# ProPrj_LED__2025-12-08-14-26-45.net
KiCad netlist of a schematic drawn in EasyEDA Pro
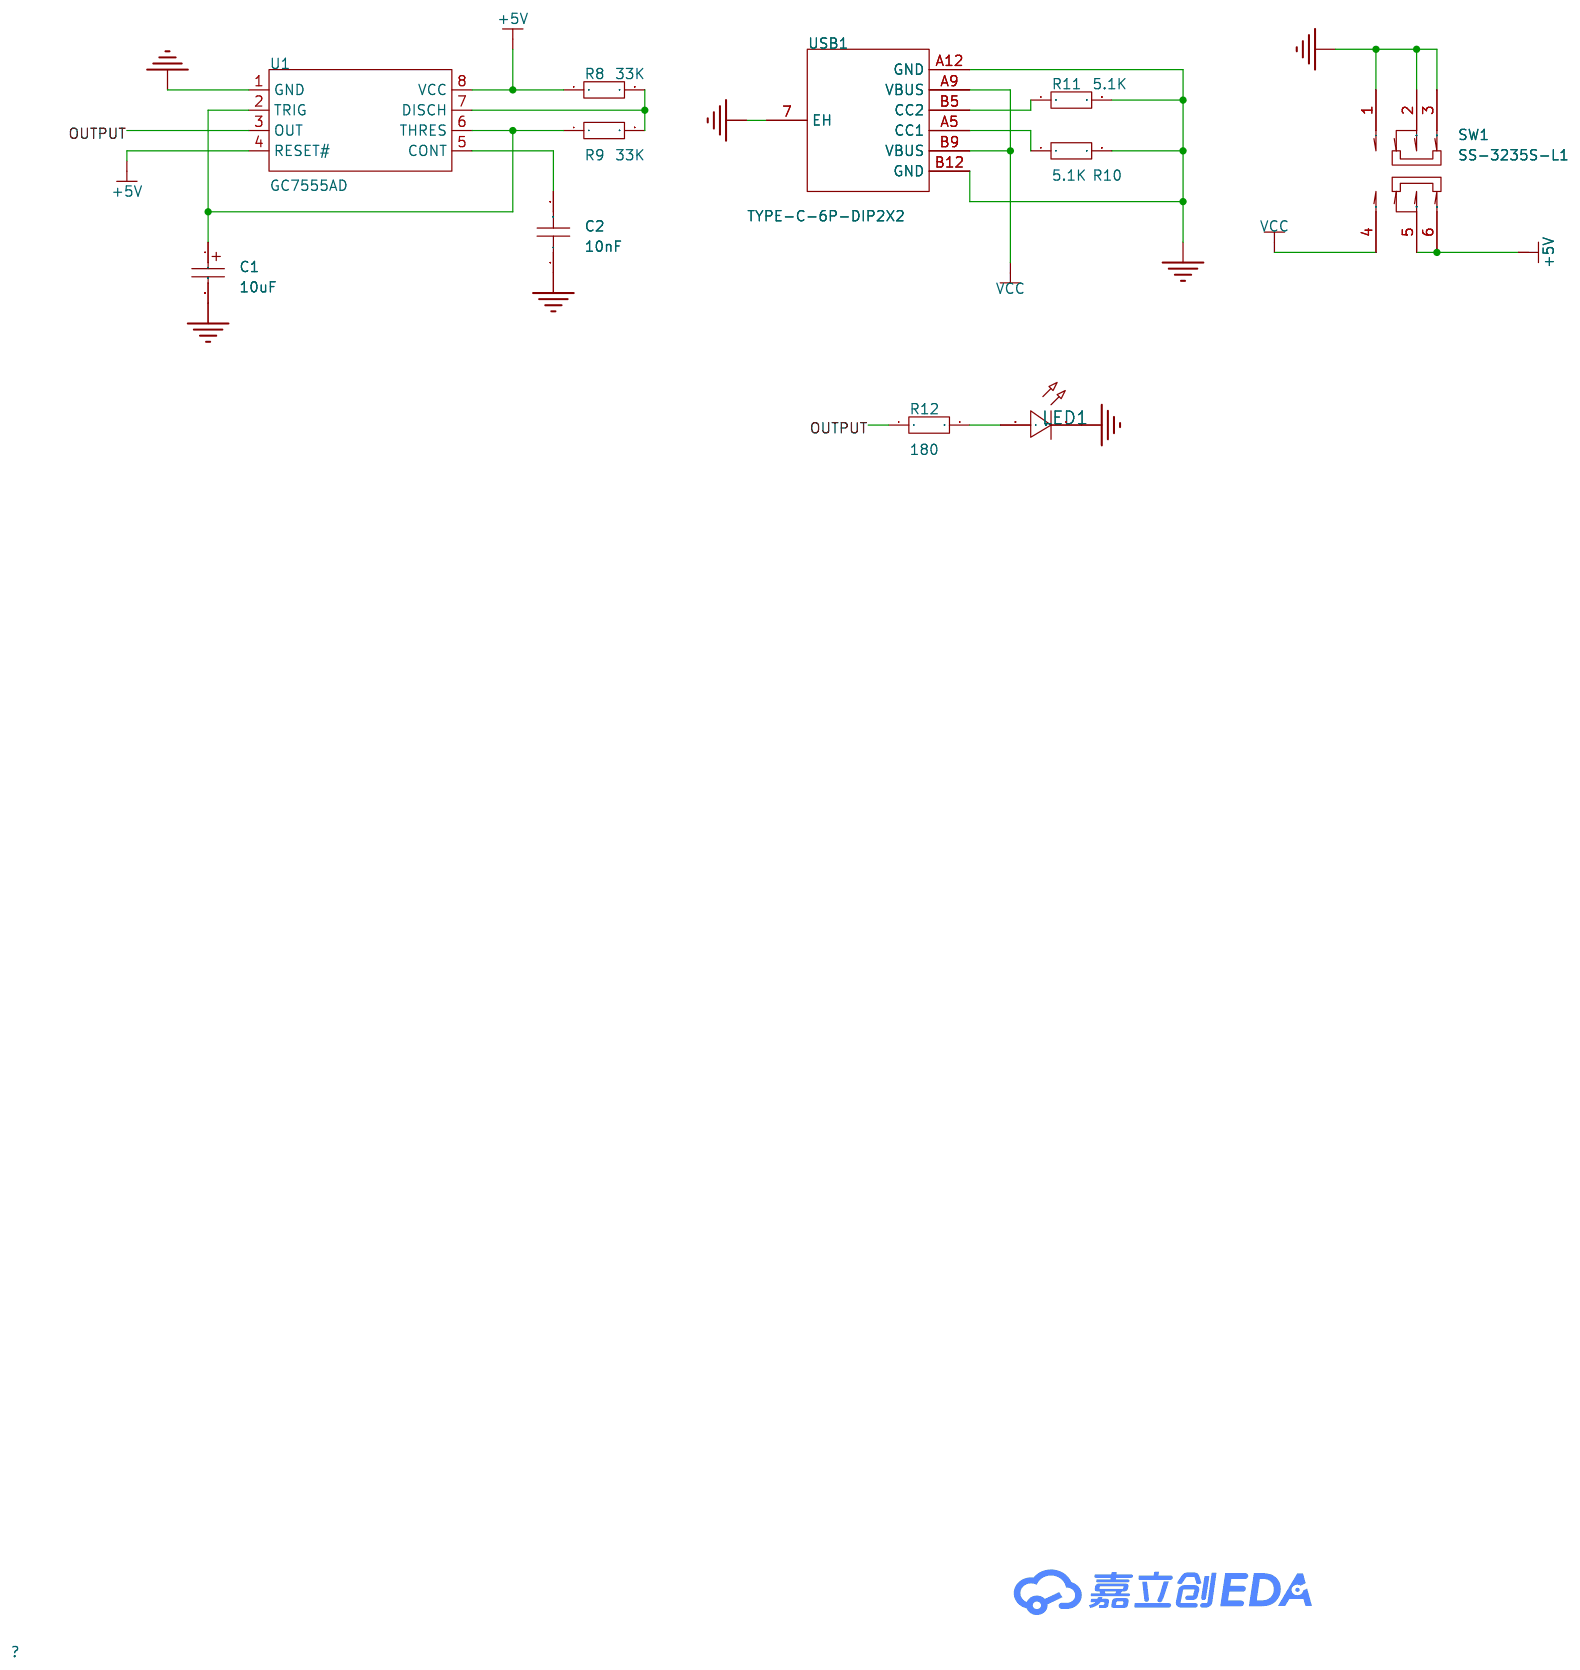
[diagram p0: schematic sheet]

(export (version "E")
  (design (tool "Eeschema 10.0.6"))
  (components
    (comp (ref "C1")
      (value "10uF")
      (footprint "easyedapro:C_Ele_SMD_3x5.4mm")
      (libsource (lib "easyedapro") (part "CAP"))
    )
    (comp (ref "C2")
      (value "10nF")
      (footprint "easyedapro:C0603")
      (libsource (lib "easyedapro") (part "Capacitance"))
    )
    (comp (ref "LED1")
      (value "~")
      (footprint "easyedapro:LED_0603")
      (libsource (lib "easyedapro") (part "LED_R"))
    )
    (comp (ref "R8") (value "33K") (footprint "easyedapro:R0805") (libsource (lib "easyedapro") (part "电阻")))
    (comp (ref "R9") (value "33K") (footprint "easyedapro:R0805") (libsource (lib "easyedapro") (part "电阻")))
    (comp (ref "R10")
      (value "5.1K")
      (footprint "easyedapro:R0805")
      (libsource (lib "easyedapro") (part "电阻"))
    )
    (comp (ref "R11")
      (value "5.1K")
      (footprint "easyedapro:R0805")
      (libsource (lib "easyedapro") (part "电阻"))
    )
    (comp (ref "R12") (value "180") (footprint "easyedapro:R0805") (libsource (lib "easyedapro") (part "电阻")))
    (comp (ref "SW1")
      (value "SS-3235S-L1")
      (footprint "easyedapro:SW-SMD_SS-3235S-LX")
      (description "电路结构:双刀双掷;安装方式:卧贴;开关颜色:黑色;额定电流:50mA;额定电压:12V;工作寿命:1万次;")
      (fields (field (name "Manufacturer") "XKB Connection(中国星坤)"))
      (libsource (lib "easyedapro") (part "SS-3235S-L1"))
    )
    (comp (ref "U1")
      (value "GC7555AD")
      (footprint "easyedapro:PDIP-8_L9.5-W6.4-P2.54-LS7.6-BL")
      (description "通用计时器：时基电路；计时；脉冲产生；满足用户（至少工业级）自主可控的需求。")
      (fields (field (name "Manufacturer") "Sungine(双竞集成)"))
      (libsource (lib "easyedapro") (part "GC7555AD"))
    )
    (comp (ref "USB1")
      (value "TYPE-C-6P-DIP2X2")
      (footprint "easyedapro:TYPE-C-SMD_TYPE-C-6P")
      (libsource (lib "easyedapro") (part "TYPE-C-6P-DIP2X2"))
    )
  )
  (nets
    (net (code "1") (name "+5V") (class "Default")
      (node (ref "R8") (pin "1") (pinfunction "1_1") (pintype "input"))
      (node (ref "SW1") (pin "5") (pinfunction "5_5") (pintype "unspecified"))
      (node (ref "SW1") (pin "6") (pinfunction "6_6") (pintype "unspecified"))
      (node (ref "U1") (pin "4") (pinfunction "RESET#_4") (pintype "unspecified"))
      (node (ref "U1") (pin "8") (pinfunction "VCC_8") (pintype "unspecified"))
    )
    (net (code "2") (name "/OUTPUT") (class "Default")
      (node (ref "R12") (pin "1") (pinfunction "1_1") (pintype "input"))
      (node (ref "U1") (pin "3") (pinfunction "OUT_3") (pintype "unspecified"))
    )
    (net (code "3") (name "GND") (class "Default")
      (node (ref "C1") (pin "2") (pinfunction "2_2") (pintype "input"))
      (node (ref "C2") (pin "1") (pinfunction "1_1") (pintype "input"))
      (node (ref "LED1") (pin "1") (pinfunction "C_1") (pintype "input"))
      (node (ref "R10") (pin "2") (pinfunction "2_2") (pintype "input"))
      (node (ref "R11") (pin "2") (pinfunction "2_2") (pintype "input"))
      (node (ref "SW1") (pin "1") (pinfunction "1_1") (pintype "unspecified"))
      (node (ref "SW1") (pin "2") (pinfunction "2_2") (pintype "unspecified"))
      (node (ref "SW1") (pin "3") (pinfunction "3_3") (pintype "unspecified"))
      (node (ref "U1") (pin "1") (pinfunction "GND_1") (pintype "unspecified"))
      (node (ref "USB1") (pin "7") (pinfunction "EH_7") (pintype "unspecified"))
      (node (ref "USB1") (pin "A12") (pinfunction "GND_A12") (pintype "unspecified"))
      (node (ref "USB1") (pin "B12") (pinfunction "GND_B12") (pintype "unspecified"))
    )
    (net (code "4") (name "Net-(LED1-A)") (class "Default")
      (node (ref "LED1") (pin "2") (pinfunction "A_2") (pintype "input"))
      (node (ref "R12") (pin "2") (pinfunction "2_2") (pintype "input"))
    )
    (net (code "5") (name "Net-(U1-CONT)") (class "Default")
      (node (ref "C2") (pin "2") (pinfunction "2_2") (pintype "input"))
      (node (ref "U1") (pin "5") (pinfunction "CONT_5") (pintype "unspecified"))
    )
    (net (code "6") (name "Net-(U1-DISCH)") (class "Default")
      (node (ref "R8") (pin "2") (pinfunction "2_2") (pintype "input"))
      (node (ref "R9") (pin "2") (pinfunction "2_2") (pintype "input"))
      (node (ref "U1") (pin "7") (pinfunction "DISCH_7") (pintype "unspecified"))
    )
    (net (code "7") (name "Net-(U1-THRES)") (class "Default")
      (node (ref "C1") (pin "1") (pinfunction "1_1") (pintype "input"))
      (node (ref "R9") (pin "1") (pinfunction "1_1") (pintype "input"))
      (node (ref "U1") (pin "2") (pinfunction "TRIG_2") (pintype "unspecified"))
      (node (ref "U1") (pin "6") (pinfunction "THRES_6") (pintype "unspecified"))
    )
    (net (code "8") (name "Net-(USB1-CC1)") (class "Default")
      (node (ref "R10") (pin "1") (pinfunction "1_1") (pintype "input"))
      (node (ref "USB1") (pin "A5") (pinfunction "CC1_A5") (pintype "unspecified"))
    )
    (net (code "9") (name "Net-(USB1-CC2)") (class "Default")
      (node (ref "R11") (pin "1") (pinfunction "1_1") (pintype "input"))
      (node (ref "USB1") (pin "B5") (pinfunction "CC2_B5") (pintype "unspecified"))
    )
    (net (code "10") (name "VCC") (class "Default")
      (node (ref "SW1") (pin "4") (pinfunction "4_4") (pintype "unspecified"))
      (node (ref "USB1") (pin "A9") (pinfunction "VBUS_A9") (pintype "unspecified"))
      (node (ref "USB1") (pin "B9") (pinfunction "VBUS_B9") (pintype "unspecified"))
    )
  )
)
